# Battery_Shield.net
KiCad netlist of a schematic drawn in EAGLE
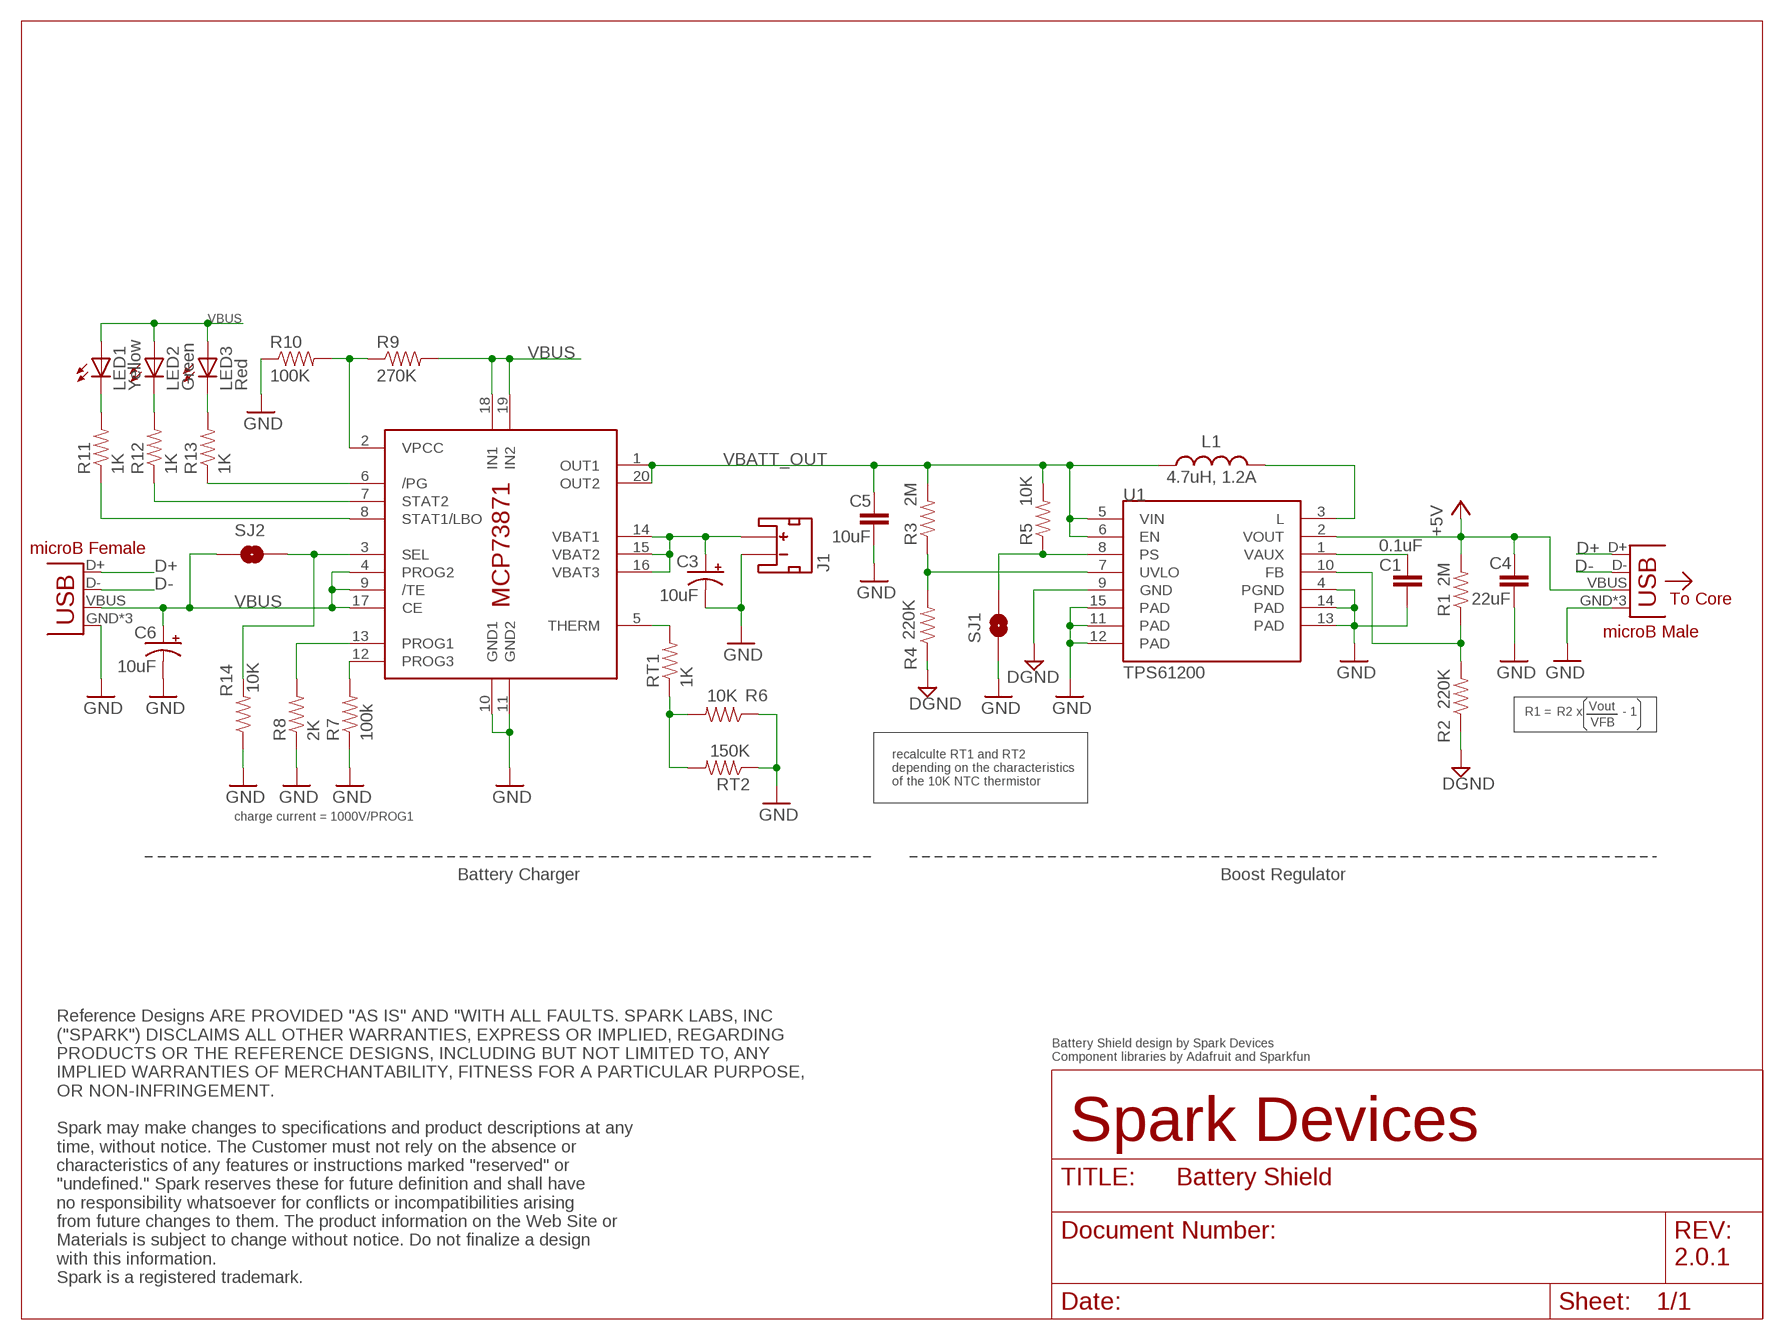
[diagram p0: schematic, sheet 1]

(export (version "E")
  (design (tool "Eeschema 10.0.6"))
  (components
    (comp (ref "C1")
      (value "0.1uF")
      (footprint "eagle-import:0402-CAP")
      (libsource (lib "eagle-import") (part "SparkFun-Passives_CAP0402-CAP"))
    )
    (comp (ref "C3")
      (value "10uF")
      (footprint "eagle-import:EIA3216")
      (libsource (lib "eagle-import") (part "10UF-16V-10%(TANT)"))
    )
    (comp (ref "C4")
      (value "22uF")
      (footprint "eagle-import:0805")
      (libsource (lib "eagle-import") (part "SparkFun-Passives_CAP0805"))
    )
    (comp (ref "C5")
      (value "10uF")
      (footprint "eagle-import:1206")
      (libsource (lib "eagle-import") (part "CAP1206"))
    )
    (comp (ref "C6")
      (value "10uF")
      (footprint "eagle-import:EIA3216")
      (fields (field (name "PROD_ID") "CAP-00811"))
      (libsource (lib "eagle-import") (part "10UF-16V-10%(TANT)"))
    )
    (comp (ref "IC1")
      (value "MCP73871")
      (footprint "eagle-import:QFN20")
      (libsource (lib "eagle-import") (part "MCP73871"))
    )
    (comp (ref "J1")
      (value "JST_2MM_MALE")
      (footprint "eagle-import:JST-2-SMD")
      (libsource (lib "eagle-import") (part "JST_2MM_MALE"))
    )
    (comp (ref "JP1")
      (value "USBUSB-MICROB-SLOT-HOLE")
      (footprint "eagle-import:USB-MICROB-SLOT-HOLE")
      (libsource (lib "eagle-import") (part "USBUSB-MICROB-SLOT-HOLE"))
    )
    (comp (ref "JP2")
      (value "USBFCI")
      (footprint "eagle-import:USB-MICROB-MALE-SANDWICH")
      (libsource (lib "eagle-import") (part "USBFCI"))
    )
    (comp (ref "L1")
      (value "4.7uH, 1.2A")
      (footprint "eagle-import:CDRH2D09")
      (libsource (lib "eagle-import") (part "INDUCTOR."))
    )
    (comp (ref "LED1")
      (value "Yellow")
      (footprint "eagle-import:LED-0603")
      (libsource (lib "eagle-import") (part "LED0603"))
    )
    (comp (ref "LED2")
      (value "Green")
      (footprint "eagle-import:LED-0603")
      (libsource (lib "eagle-import") (part "LED0603"))
    )
    (comp (ref "LED3")
      (value "Red")
      (footprint "eagle-import:LED-0603")
      (libsource (lib "eagle-import") (part "LED0603"))
    )
    (comp (ref "R1")
      (value "2M")
      (footprint "eagle-import:0402-RES")
      (libsource (lib "eagle-import") (part "RESISTOR0402-RES"))
    )
    (comp (ref "R2")
      (value "220K")
      (footprint "eagle-import:0402-RES")
      (libsource (lib "eagle-import") (part "RESISTOR0402-RES"))
    )
    (comp (ref "R3")
      (value "2M")
      (footprint "eagle-import:0402-RES")
      (libsource (lib "eagle-import") (part "RESISTOR0402-RES"))
    )
    (comp (ref "R4")
      (value "220K")
      (footprint "eagle-import:0402-RES")
      (libsource (lib "eagle-import") (part "RESISTOR0402-RES"))
    )
    (comp (ref "R5")
      (value "10K")
      (footprint "eagle-import:0402-RES")
      (libsource (lib "eagle-import") (part "RESISTOR0402-RES"))
    )
    (comp (ref "R6")
      (value "10K")
      (footprint "eagle-import:0402-RES")
      (libsource (lib "eagle-import") (part "RESISTOR0402-RES"))
    )
    (comp (ref "R7")
      (value "100k")
      (footprint "eagle-import:0402-RES")
      (libsource (lib "eagle-import") (part "RESISTOR0402-RES"))
    )
    (comp (ref "R8")
      (value "2K")
      (footprint "eagle-import:0402-RES")
      (libsource (lib "eagle-import") (part "RESISTOR0402-RES"))
    )
    (comp (ref "R9")
      (value "270K")
      (footprint "eagle-import:0402-RES")
      (libsource (lib "eagle-import") (part "RESISTOR0402-RES"))
    )
    (comp (ref "R10")
      (value "100K")
      (footprint "eagle-import:0402-RES")
      (libsource (lib "eagle-import") (part "RESISTOR0402-RES"))
    )
    (comp (ref "R11")
      (value "1K")
      (footprint "eagle-import:0402-RES")
      (libsource (lib "eagle-import") (part "RESISTOR0402-RES"))
    )
    (comp (ref "R12")
      (value "1K")
      (footprint "eagle-import:0402-RES")
      (libsource (lib "eagle-import") (part "RESISTOR0402-RES"))
    )
    (comp (ref "R13")
      (value "1K")
      (footprint "eagle-import:0402-RES")
      (libsource (lib "eagle-import") (part "RESISTOR0402-RES"))
    )
    (comp (ref "R14")
      (value "10K")
      (footprint "eagle-import:0402-RES")
      (libsource (lib "eagle-import") (part "RESISTOR0402-RES"))
    )
    (comp (ref "RT1")
      (value "1K")
      (footprint "eagle-import:0402-RES")
      (libsource (lib "eagle-import") (part "RESISTOR0402-RES"))
    )
    (comp (ref "RT2")
      (value "150K")
      (footprint "eagle-import:0402-RES")
      (libsource (lib "eagle-import") (part "RESISTOR0402-RES"))
    )
    (comp (ref "SJ1")
      (value "SOLDERJUMPERNO")
      (footprint "eagle-import:SJ_2S-NO")
      (libsource (lib "eagle-import") (part "SOLDERJUMPERNO"))
    )
    (comp (ref "SJ2")
      (value "SOLDERJUMPERNO")
      (footprint "eagle-import:SJ_2S-NO")
      (libsource (lib "eagle-import") (part "SOLDERJUMPERNO"))
    )
    (comp (ref "U1")
      (value "TPS61200")
      (footprint "eagle-import:QFN-10_PAD")
      (libsource (lib "eagle-import") (part "TPS61200"))
    )
  )
  (nets
    (net (code "1") (name "+5V") (class "Default")
      (node (ref "C4") (pin "1") (pinfunction "1_1") (pintype "passive"))
      (node (ref "JP2") (pin "VBUS") (pinfunction "VBUS_VBUS") (pintype "bidirectional"))
      (node (ref "R1") (pin "2") (pinfunction "2_2") (pintype "passive"))
      (node (ref "U1") (pin "2") (pinfunction "VOUT_2") (pintype "passive"))
    )
    (net (code "2") (name "/D+") (class "Default")
      (node (ref "JP1") (pin "D+") (pinfunction "D+_D+") (pintype "bidirectional"))
      (node (ref "JP2") (pin "D+") (pinfunction "D+_D+") (pintype "bidirectional"))
    )
    (net (code "3") (name "/D-") (class "Default")
      (node (ref "JP1") (pin "D-") (pinfunction "D-_D-") (pintype "bidirectional"))
      (node (ref "JP2") (pin "D-") (pinfunction "D-_D-") (pintype "bidirectional"))
    )
    (net (code "4") (name "/VBATT_OUT") (class "Default")
      (node (ref "C5") (pin "1") (pinfunction "1_1") (pintype "passive"))
      (node (ref "IC1") (pin "1") (pinfunction "OUT1_1") (pintype "output"))
      (node (ref "IC1") (pin "20") (pinfunction "OUT2_20") (pintype "output"))
      (node (ref "L1") (pin "P$1") (pinfunction "1_P$1") (pintype "passive"))
      (node (ref "R3") (pin "2") (pinfunction "2_2") (pintype "passive"))
      (node (ref "R5") (pin "2") (pinfunction "2_2") (pintype "passive"))
      (node (ref "U1") (pin "5") (pinfunction "VIN_5") (pintype "power_in"))
      (node (ref "U1") (pin "6") (pinfunction "EN_6") (pintype "input"))
    )
    (net (code "5") (name "/VBUS") (class "Default")
      (node (ref "C6") (pin "A") (pinfunction "+_A") (pintype "passive"))
      (node (ref "IC1") (pin "17") (pinfunction "CE_17") (pintype "input"))
      (node (ref "IC1") (pin "18") (pinfunction "IN1_18") (pintype "input"))
      (node (ref "IC1") (pin "19") (pinfunction "IN2_19") (pintype "input"))
      (node (ref "IC1") (pin "4") (pinfunction "PROG2_4") (pintype "input"))
      (node (ref "IC1") (pin "9") (pinfunction "/TE_9") (pintype "input"))
      (node (ref "JP1") (pin "VBUS") (pinfunction "VBUS_VBUS") (pintype "bidirectional"))
      (node (ref "LED1") (pin "A") (pinfunction "A_A") (pintype "passive"))
      (node (ref "LED2") (pin "A") (pinfunction "A_A") (pintype "passive"))
      (node (ref "LED3") (pin "A") (pinfunction "A_A") (pintype "passive"))
      (node (ref "R9") (pin "2") (pinfunction "2_2") (pintype "passive"))
      (node (ref "SJ2") (pin "1") (pinfunction "1_1") (pintype "passive"))
    )
    (net (code "6") (name "DGND") (class "Default")
      (node (ref "R2") (pin "1") (pinfunction "1_1") (pintype "passive"))
      (node (ref "R4") (pin "1") (pinfunction "1_1") (pintype "passive"))
      (node (ref "U1") (pin "9") (pinfunction "GND_9") (pintype "power_in"))
    )
    (net (code "7") (name "GND") (class "Default")
      (node (ref "C1") (pin "2") (pinfunction "2_2") (pintype "passive"))
      (node (ref "C3") (pin "C") (pinfunction "-_C") (pintype "passive"))
      (node (ref "C4") (pin "2") (pinfunction "2_2") (pintype "passive"))
      (node (ref "C5") (pin "2") (pinfunction "2_2") (pintype "passive"))
      (node (ref "C6") (pin "C") (pinfunction "-_C") (pintype "passive"))
      (node (ref "IC1") (pin "10") (pinfunction "GND1_10") (pintype "power_in"))
      (node (ref "IC1") (pin "11") (pinfunction "GND2_11") (pintype "power_in"))
      (node (ref "J1") (pin "1") (pinfunction "-_1") (pintype "bidirectional"))
      (node (ref "JP1") (pin "GND") (pinfunction "GND_GND") (pintype "bidirectional"))
      (node (ref "JP1") (pin "MT1") (pinfunction "GND_MT1") (pintype "bidirectional"))
      (node (ref "JP1") (pin "MT2") (pinfunction "GND_MT2") (pintype "bidirectional"))
      (node (ref "JP2") (pin "GND") (pinfunction "GND_GND") (pintype "bidirectional"))
      (node (ref "JP2") (pin "GNDPAD1") (pinfunction "GND_GNDPAD1") (pintype "bidirectional"))
      (node (ref "JP2") (pin "GNDPAD2") (pinfunction "GND_GNDPAD2") (pintype "bidirectional"))
      (node (ref "R10") (pin "1") (pinfunction "1_1") (pintype "passive"))
      (node (ref "R14") (pin "1") (pinfunction "1_1") (pintype "passive"))
      (node (ref "R6") (pin "1") (pinfunction "1_1") (pintype "passive"))
      (node (ref "R7") (pin "1") (pinfunction "1_1") (pintype "passive"))
      (node (ref "R8") (pin "1") (pinfunction "1_1") (pintype "passive"))
      (node (ref "RT2") (pin "1") (pinfunction "1_1") (pintype "passive"))
      (node (ref "SJ1") (pin "1") (pinfunction "1_1") (pintype "passive"))
      (node (ref "U1") (pin "11") (pinfunction "PAD_11") (pintype "power_in"))
      (node (ref "U1") (pin "12") (pinfunction "PAD_12") (pintype "power_in"))
      (node (ref "U1") (pin "13") (pinfunction "PAD_13") (pintype "power_in"))
      (node (ref "U1") (pin "14") (pinfunction "PAD_14") (pintype "power_in"))
      (node (ref "U1") (pin "15") (pinfunction "PAD_15") (pintype "power_in"))
      (node (ref "U1") (pin "4") (pinfunction "PGND_4") (pintype "power_in"))
    )
    (net (code "8") (name "Net-(C3-+)") (class "Default")
      (node (ref "C3") (pin "A") (pinfunction "+_A") (pintype "passive"))
      (node (ref "IC1") (pin "14") (pinfunction "VBAT1_14") (pintype "output"))
      (node (ref "IC1") (pin "15") (pinfunction "VBAT2_15") (pintype "output"))
      (node (ref "IC1") (pin "16") (pinfunction "VBAT3_16") (pintype "output"))
      (node (ref "J1") (pin "2") (pinfunction "+_2") (pintype "bidirectional"))
    )
    (net (code "9") (name "Net-(IC1-PROG1)") (class "Default")
      (node (ref "IC1") (pin "13") (pinfunction "PROG1_13") (pintype "input"))
      (node (ref "R8") (pin "2") (pinfunction "2_2") (pintype "passive"))
    )
    (net (code "10") (name "Net-(IC1-PROG3)") (class "Default")
      (node (ref "IC1") (pin "12") (pinfunction "PROG3_12") (pintype "input"))
      (node (ref "R7") (pin "2") (pinfunction "2_2") (pintype "passive"))
    )
    (net (code "11") (name "Net-(IC1-SEL)") (class "Default")
      (node (ref "IC1") (pin "3") (pinfunction "SEL_3") (pintype "input"))
      (node (ref "R14") (pin "2") (pinfunction "2_2") (pintype "passive"))
      (node (ref "SJ2") (pin "2") (pinfunction "2_2") (pintype "passive"))
    )
    (net (code "12") (name "Net-(IC1-STAT1{slash}LBO)") (class "Default")
      (node (ref "IC1") (pin "8") (pinfunction "STAT1/LBO_8") (pintype "output"))
      (node (ref "R11") (pin "1") (pinfunction "1_1") (pintype "passive"))
    )
    (net (code "13") (name "Net-(IC1-STAT2)") (class "Default")
      (node (ref "IC1") (pin "7") (pinfunction "STAT2_7") (pintype "output"))
      (node (ref "R12") (pin "1") (pinfunction "1_1") (pintype "passive"))
    )
    (net (code "14") (name "Net-(IC1-THERM)") (class "Default")
      (node (ref "IC1") (pin "5") (pinfunction "THERM_5") (pintype "input"))
      (node (ref "RT1") (pin "2") (pinfunction "2_2") (pintype "passive"))
    )
    (net (code "15") (name "Net-(IC1-VPCC)") (class "Default")
      (node (ref "IC1") (pin "2") (pinfunction "VPCC_2") (pintype "input"))
      (node (ref "R10") (pin "2") (pinfunction "2_2") (pintype "passive"))
      (node (ref "R9") (pin "1") (pinfunction "1_1") (pintype "passive"))
    )
    (net (code "16") (name "Net-(IC1-{slash}PG)") (class "Default")
      (node (ref "IC1") (pin "6") (pinfunction "/PG_6") (pintype "output"))
      (node (ref "R13") (pin "1") (pinfunction "1_1") (pintype "passive"))
    )
    (net (code "17") (name "Net-(L1-2)") (class "Default")
      (node (ref "L1") (pin "P$2") (pinfunction "2_P$2") (pintype "passive"))
      (node (ref "U1") (pin "3") (pinfunction "L_3") (pintype "passive"))
    )
    (net (code "18") (name "Net-(LED1-PadC)") (class "Default")
      (node (ref "LED1") (pin "C") (pinfunction "C_C") (pintype "passive"))
      (node (ref "R11") (pin "2") (pinfunction "2_2") (pintype "passive"))
    )
    (net (code "19") (name "Net-(LED2-PadC)") (class "Default")
      (node (ref "LED2") (pin "C") (pinfunction "C_C") (pintype "passive"))
      (node (ref "R12") (pin "2") (pinfunction "2_2") (pintype "passive"))
    )
    (net (code "20") (name "Net-(LED3-PadC)") (class "Default")
      (node (ref "LED3") (pin "C") (pinfunction "C_C") (pintype "passive"))
      (node (ref "R13") (pin "2") (pinfunction "2_2") (pintype "passive"))
    )
    (net (code "21") (name "Net-(R6-Pad2)") (class "Default")
      (node (ref "R6") (pin "2") (pinfunction "2_2") (pintype "passive"))
      (node (ref "RT1") (pin "1") (pinfunction "1_1") (pintype "passive"))
      (node (ref "RT2") (pin "2") (pinfunction "2_2") (pintype "passive"))
    )
    (net (code "22") (name "Net-(U1-FB)") (class "Default")
      (node (ref "R1") (pin "1") (pinfunction "1_1") (pintype "passive"))
      (node (ref "R2") (pin "2") (pinfunction "2_2") (pintype "passive"))
      (node (ref "U1") (pin "10") (pinfunction "FB_10") (pintype "passive"))
    )
    (net (code "23") (name "Net-(U1-PS)") (class "Default")
      (node (ref "R5") (pin "1") (pinfunction "1_1") (pintype "passive"))
      (node (ref "SJ1") (pin "2") (pinfunction "2_2") (pintype "passive"))
      (node (ref "U1") (pin "8") (pinfunction "PS_8") (pintype "input"))
    )
    (net (code "24") (name "Net-(U1-UVLO)") (class "Default")
      (node (ref "R3") (pin "1") (pinfunction "1_1") (pintype "passive"))
      (node (ref "R4") (pin "2") (pinfunction "2_2") (pintype "passive"))
      (node (ref "U1") (pin "7") (pinfunction "UVLO_7") (pintype "passive"))
    )
    (net (code "25") (name "Net-(U1-VAUX)") (class "Default")
      (node (ref "C1") (pin "1") (pinfunction "1_1") (pintype "passive"))
      (node (ref "U1") (pin "1") (pinfunction "VAUX_1") (pintype "passive"))
    )
    (net (code "26") (name "unconnected-(J1-PAD1-PadNC1)") (class "Default")
      (node (ref "J1") (pin "NC1") (pinfunction "PAD1_NC1") (pintype "bidirectional"))
    )
    (net (code "27") (name "unconnected-(J1-PAD2-PadNC2)") (class "Default")
      (node (ref "J1") (pin "NC2") (pinfunction "PAD2_NC2") (pintype "bidirectional"))
    )
  )
)
